# 3_DEBUG_SD__RTC.net
KiCad netlist of a schematic drawn in Altium Designer
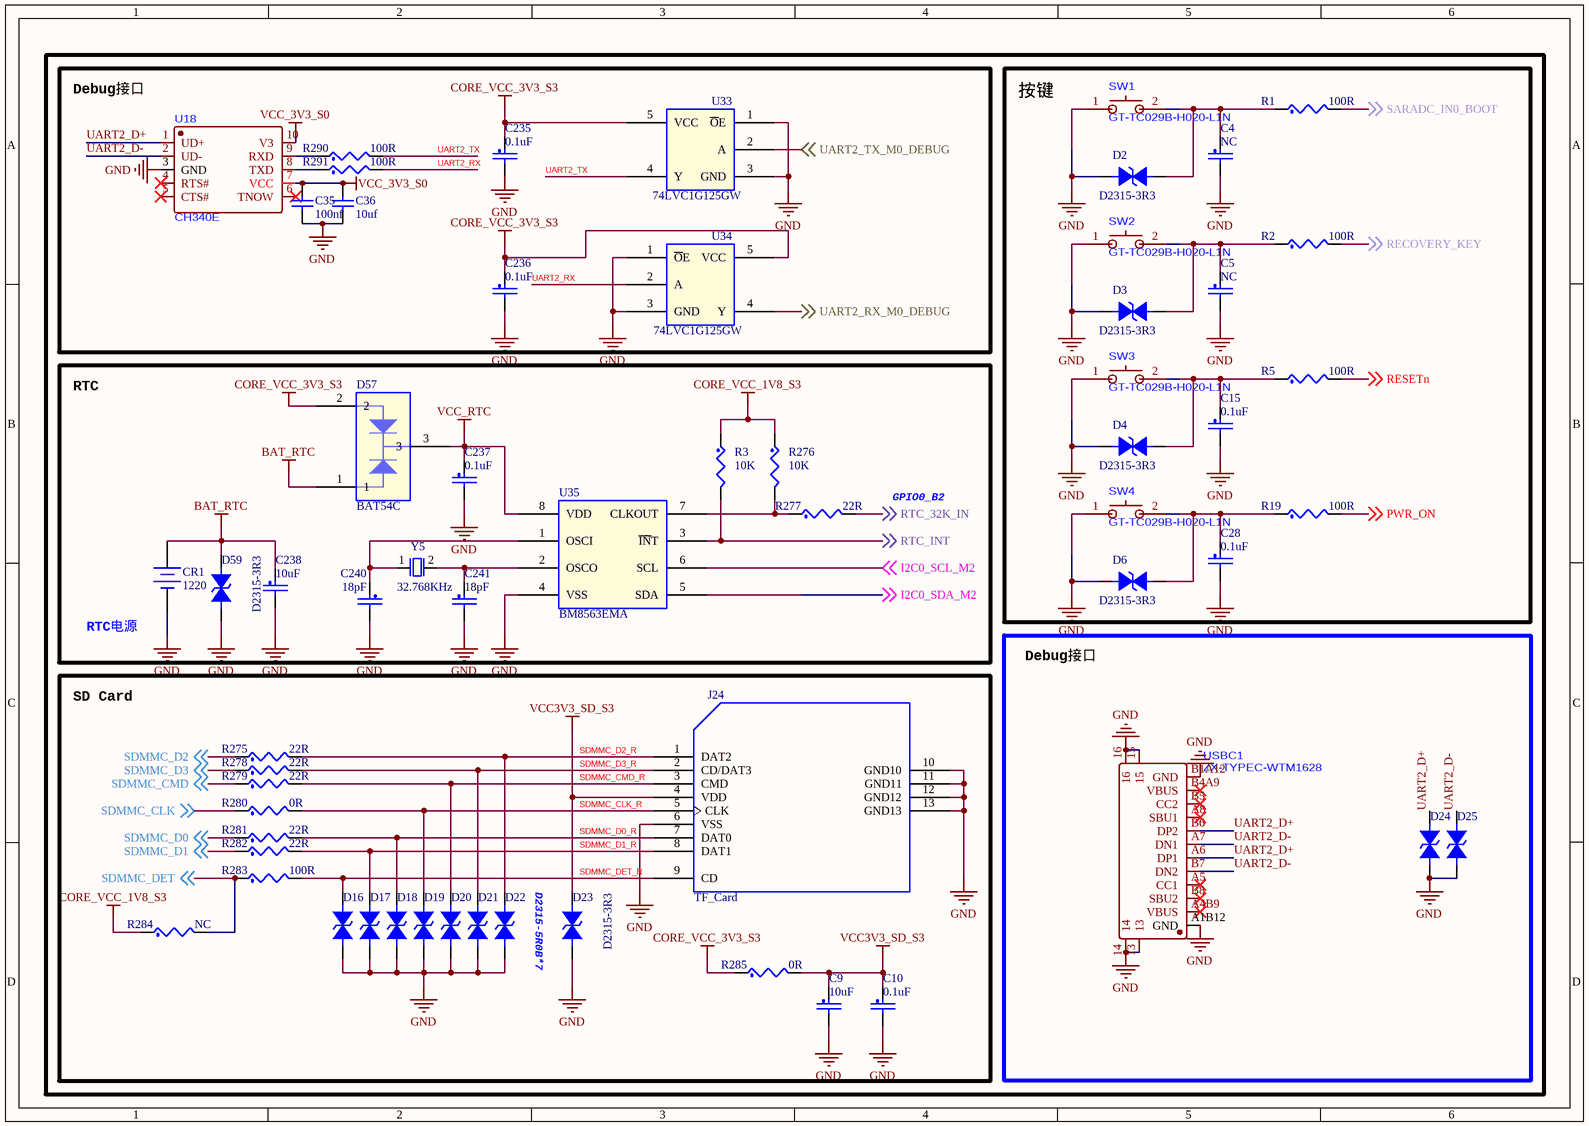
[diagram p0: 3.DEBUG_SD卡_RTC_按键.SchDoc]

(export (version "E")
  (design (tool "Eeschema 10.0.6"))
  (components
    (comp (ref "C4") (value "NC") (footprint "0.PCB1:C0402") (libsource (lib "RK3588底板") (part "CAP_NP")))
    (comp (ref "C5") (value "NC") (footprint "0.PCB1:C0402") (libsource (lib "RK3588底板") (part "CAP_NP")))
    (comp (ref "C9") (value "10uF") (footprint "0.PCB1:C0402") (libsource (lib "RK3588底板") (part "CAP_NP")))
    (comp (ref "C10") (value "0.1uF") (footprint "0.PCB1:C0402") (libsource (lib "RK3588底板") (part "CAP_NP")))
    (comp (ref "C15") (value "0.1uF") (footprint "0.PCB1:C0402") (libsource (lib "RK3588底板") (part "CAP_NP")))
    (comp (ref "C28") (value "0.1uF") (footprint "0.PCB1:C0402") (libsource (lib "RK3588底板") (part "CAP_NP")))
    (comp (ref "C35")
      (value "100nf")
      (footprint "0.PCB1:C0603_L")
      (description "贴片电容/MLCC电容")
      (libsource (lib "RK3588底板") (part "C"))
    )
    (comp (ref "C36")
      (value "10uf")
      (footprint "0.PCB1:C0603_L")
      (description "贴片电容/MLCC电容")
      (libsource (lib "RK3588底板") (part "C"))
    )
    (comp (ref "C235")
      (value "0.1uF")
      (footprint "0.PCB1:C0402")
      (libsource (lib "RK3588底板") (part "CAP_NP"))
    )
    (comp (ref "C236")
      (value "0.1uF")
      (footprint "0.PCB1:C0402")
      (libsource (lib "RK3588底板") (part "CAP_NP"))
    )
    (comp (ref "C237")
      (value "0.1uF")
      (footprint "0.PCB1:C0402")
      (libsource (lib "RK3588底板") (part "CAP_NP"))
    )
    (comp (ref "C238") (value "10uF") (footprint "0.PCB1:C0402") (libsource (lib "RK3588底板") (part "CAP_NP")))
    (comp (ref "C240") (value "18pF") (footprint "0.PCB1:C0402") (libsource (lib "RK3588底板") (part "CAP_NP")))
    (comp (ref "C241") (value "18pF") (footprint "0.PCB1:C0402") (libsource (lib "RK3588底板") (part "CAP_NP")))
    (comp (ref "CR1")
      (value "1220")
      (footprint "0.PCB1:CR1220_A")
      (description "微型电池")
      (libsource (lib "RK3588底板") (part "BAT_CR1220_CR2032"))
    )
    (comp (ref "D2")
      (value "D2315-3R3")
      (footprint "0.PCB1:esd0402")
      (libsource (lib "RK3588底板") (part "DIODE BI-DIR TRIG"))
    )
    (comp (ref "D3")
      (value "D2315-3R3")
      (footprint "0.PCB1:esd0402")
      (libsource (lib "RK3588底板") (part "DIODE BI-DIR TRIG"))
    )
    (comp (ref "D4")
      (value "D2315-3R3")
      (footprint "0.PCB1:esd0402")
      (libsource (lib "RK3588底板") (part "DIODE BI-DIR TRIG"))
    )
    (comp (ref "D6")
      (value "D2315-3R3")
      (footprint "0.PCB1:esd0402")
      (libsource (lib "RK3588底板") (part "DIODE BI-DIR TRIG"))
    )
    (comp (ref "D16")
      (value "D2315-5R0B")
      (footprint "0.PCB1:esd0402")
      (libsource (lib "RK3588底板") (part "DIODE BI-DIR TRIG"))
    )
    (comp (ref "D17")
      (value "D2315-5R0B")
      (footprint "0.PCB1:esd0402")
      (libsource (lib "RK3588底板") (part "DIODE BI-DIR TRIG"))
    )
    (comp (ref "D18")
      (value "D2315-5R0B")
      (footprint "0.PCB1:esd0402")
      (libsource (lib "RK3588底板") (part "DIODE BI-DIR TRIG"))
    )
    (comp (ref "D19")
      (value "D2315-5R0B")
      (footprint "0.PCB1:esd0402")
      (libsource (lib "RK3588底板") (part "DIODE BI-DIR TRIG"))
    )
    (comp (ref "D20")
      (value "D2315-5R0B")
      (footprint "0.PCB1:esd0402")
      (libsource (lib "RK3588底板") (part "DIODE BI-DIR TRIG"))
    )
    (comp (ref "D21")
      (value "D2315-5R0B")
      (footprint "0.PCB1:esd0402")
      (libsource (lib "RK3588底板") (part "DIODE BI-DIR TRIG"))
    )
    (comp (ref "D22")
      (value "D2315-5R0B")
      (footprint "0.PCB1:esd0402")
      (libsource (lib "RK3588底板") (part "DIODE BI-DIR TRIG"))
    )
    (comp (ref "D23")
      (value "D2315-3R3")
      (footprint "0.PCB1:esd0402")
      (libsource (lib "RK3588底板") (part "DIODE BI-DIR TRIG"))
    )
    (comp (ref "D24")
      (value "D2315-5R0B")
      (footprint "0.PCB1:esd0402")
      (libsource (lib "RK3588底板") (part "DIODE BI-DIR TRIG"))
    )
    (comp (ref "D25")
      (value "D2315-5R0B")
      (footprint "0.PCB1:esd0402")
      (libsource (lib "RK3588底板") (part "DIODE BI-DIR TRIG"))
    )
    (comp (ref "D57")
      (value "BAT54C")
      (footprint "0.PCB1:SOT23")
      (libsource (lib "RK3588底板") (part "BAT54C"))
    )
    (comp (ref "D59")
      (value "D2315-3R3")
      (footprint "0.PCB1:esd0402")
      (libsource (lib "RK3588底板") (part "DIODE BI-DIR TRIG"))
    )
    (comp (ref "J24")
      (value "TF_Card")
      (footprint "0.PCB1:TFCARD")
      (libsource (lib "RK3588底板") (part "TF_Card"))
    )
    (comp (ref "R1") (value "100R") (footprint "0.PCB1:R0402") (libsource (lib "RK3588底板") (part "RES")))
    (comp (ref "R2") (value "100R") (footprint "0.PCB1:R0402") (libsource (lib "RK3588底板") (part "RES")))
    (comp (ref "R3") (value "10K") (footprint "0.PCB1:R0402") (libsource (lib "RK3588底板") (part "RES")))
    (comp (ref "R5") (value "100R") (footprint "0.PCB1:R0402") (libsource (lib "RK3588底板") (part "RES")))
    (comp (ref "R19") (value "100R") (footprint "0.PCB1:R0402") (libsource (lib "RK3588底板") (part "RES")))
    (comp (ref "R275") (value "22R") (footprint "0.PCB1:R0402") (libsource (lib "RK3588底板") (part "RES")))
    (comp (ref "R276") (value "10K") (footprint "0.PCB1:R0402") (libsource (lib "RK3588底板") (part "RES")))
    (comp (ref "R277") (value "22R") (footprint "0.PCB1:R0402") (libsource (lib "RK3588底板") (part "RES")))
    (comp (ref "R278") (value "22R") (footprint "0.PCB1:R0402") (libsource (lib "RK3588底板") (part "RES")))
    (comp (ref "R279") (value "22R") (footprint "0.PCB1:R0402") (libsource (lib "RK3588底板") (part "RES")))
    (comp (ref "R280") (value "0R") (footprint "0.PCB1:R0402") (libsource (lib "RK3588底板") (part "RES")))
    (comp (ref "R281") (value "22R") (footprint "0.PCB1:R0402") (libsource (lib "RK3588底板") (part "RES")))
    (comp (ref "R282") (value "22R") (footprint "0.PCB1:R0402") (libsource (lib "RK3588底板") (part "RES")))
    (comp (ref "R283") (value "100R") (footprint "0.PCB1:R0402") (libsource (lib "RK3588底板") (part "RES")))
    (comp (ref "R284") (value "NC") (footprint "0.PCB1:R0402") (libsource (lib "RK3588底板") (part "RES")))
    (comp (ref "R285") (value "0R") (footprint "0.PCB1:R0402") (libsource (lib "RK3588底板") (part "RES")))
    (comp (ref "R290") (value "100R") (footprint "0.PCB1:R0402") (libsource (lib "RK3588底板") (part "RES")))
    (comp (ref "R291") (value "100R") (footprint "0.PCB1:R0402") (libsource (lib "RK3588底板") (part "RES")))
    (comp (ref "SW1")
      (value "GT-TC029B-H020-L1N")
      (footprint "0.PCB1:SW-SMD_L3.9-W2.9-P4.15-LS5.0")
      (libsource (lib "RK3588底板") (part "GT-TC029B-H020-L1N"))
    )
    (comp (ref "SW2")
      (value "GT-TC029B-H020-L1N")
      (footprint "0.PCB1:SW-SMD_L3.9-W2.9-P4.15-LS5.0")
      (libsource (lib "RK3588底板") (part "GT-TC029B-H020-L1N"))
    )
    (comp (ref "SW3")
      (value "GT-TC029B-H020-L1N")
      (footprint "0.PCB1:SW-SMD_L3.9-W2.9-P4.15-LS5.0")
      (libsource (lib "RK3588底板") (part "GT-TC029B-H020-L1N"))
    )
    (comp (ref "SW4")
      (value "GT-TC029B-H020-L1N")
      (footprint "0.PCB1:SW-SMD_L3.9-W2.9-P4.15-LS5.0")
      (libsource (lib "RK3588底板") (part "GT-TC029B-H020-L1N"))
    )
    (comp (ref "U18")
      (value "CH340E")
      (footprint "0.PCB1:MSOP-10_L3.0-W3.0-P0.50-LS5.0-BL")
      (libsource (lib "RK3588底板") (part "CH340E"))
    )
    (comp (ref "U33")
      (value "74LVC1G125GW")
      (footprint "0.PCB1:SOT-353")
      (libsource (lib "") (part "74LVC1G125_1"))
    )
    (comp (ref "U34")
      (value "74LVC1G125GW")
      (footprint "0.PCB1:SOT-353")
      (libsource (lib "RK3588底板") (part "74LVC1G125"))
    )
    (comp (ref "U35")
      (value "BM8563EMA")
      (footprint "0.PCB1:msop-8")
      (libsource (lib "RK3588底板") (part "HYM8563S"))
    )
    (comp (ref "USBC1")
      (value "ZX-TYPEC-WTM1628")
      (footprint "0.PCB1:USB-C-SMD_ZX-TYPEC-WTM1628")
      (libsource (lib "RK3588底板") (part "ZX-TYPEC-WTM1628"))
    )
    (comp (ref "Y5")
      (value "32.768KHz")
      (footprint "0.PCB1:3215")
      (libsource (lib "RK3588底板") (part "CRYSTAL_2P"))
    )
  )
  (nets
    (net (code "1") (name "/SDMMC_CLK_R") (class "Default")
      (node (ref "D19") (pin "2") (pinfunction "2_2") (pintype "passive"))
      (node (ref "J24") (pin "5") (pinfunction "CLK_5") (pintype "passive"))
      (node (ref "R280") (pin "2") (pinfunction "2_2") (pintype "passive"))
    )
    (net (code "2") (name "/SDMMC_CMD_R") (class "Default")
      (node (ref "D20") (pin "2") (pinfunction "2_2") (pintype "passive"))
      (node (ref "J24") (pin "3") (pinfunction "CMD_3") (pintype "passive"))
      (node (ref "R279") (pin "2") (pinfunction "2_2") (pintype "passive"))
    )
    (net (code "3") (name "/SDMMC_D0_R") (class "Default")
      (node (ref "D18") (pin "2") (pinfunction "2_2") (pintype "passive"))
      (node (ref "J24") (pin "7") (pinfunction "DAT0_7") (pintype "passive"))
      (node (ref "R281") (pin "2") (pinfunction "2_2") (pintype "passive"))
    )
    (net (code "4") (name "/SDMMC_D1_R") (class "Default")
      (node (ref "D17") (pin "2") (pinfunction "2_2") (pintype "passive"))
      (node (ref "J24") (pin "8") (pinfunction "DAT1_8") (pintype "passive"))
      (node (ref "R282") (pin "2") (pinfunction "2_2") (pintype "passive"))
    )
    (net (code "5") (name "/SDMMC_D2_R") (class "Default")
      (node (ref "D22") (pin "2") (pinfunction "2_2") (pintype "passive"))
      (node (ref "J24") (pin "1") (pinfunction "DAT2_1") (pintype "passive"))
      (node (ref "R275") (pin "2") (pinfunction "2_2") (pintype "passive"))
    )
    (net (code "6") (name "/SDMMC_D3_R") (class "Default")
      (node (ref "D21") (pin "2") (pinfunction "2_2") (pintype "passive"))
      (node (ref "J24") (pin "2") (pinfunction "CD/DAT3_2") (pintype "passive"))
      (node (ref "R278") (pin "2") (pinfunction "2_2") (pintype "passive"))
    )
    (net (code "7") (name "/SDMMC_DET_R") (class "Default")
      (node (ref "D16") (pin "2") (pinfunction "2_2") (pintype "passive"))
      (node (ref "J24") (pin "9") (pinfunction "CD_9") (pintype "passive"))
      (node (ref "R283") (pin "2") (pinfunction "2_2") (pintype "passive"))
    )
    (net (code "8") (name "/UART2_D+") (class "Default")
      (node (ref "D24") (pin "2") (pinfunction "2_2") (pintype "passive"))
      (node (ref "U18") (pin "1") (pinfunction "UD+_1") (pintype "passive"))
      (node (ref "USBC1") (pin "A6") (pinfunction "DP1_A6") (pintype "passive"))
      (node (ref "USBC1") (pin "B6") (pinfunction "DP2_B6") (pintype "passive"))
    )
    (net (code "9") (name "/UART2_D-") (class "Default")
      (node (ref "D25") (pin "2") (pinfunction "2_2") (pintype "passive"))
      (node (ref "U18") (pin "2") (pinfunction "UD-_2") (pintype "passive"))
      (node (ref "USBC1") (pin "A7") (pinfunction "DN1_A7") (pintype "passive"))
      (node (ref "USBC1") (pin "B7") (pinfunction "DN2_B7") (pintype "passive"))
    )
    (net (code "10") (name "/UART2_RX") (class "Default")
      (node (ref "R291") (pin "2") (pinfunction "2_2") (pintype "passive"))
      (node (ref "U34") (pin "2") (pinfunction "A_2") (pintype "passive"))
    )
    (net (code "11") (name "/UART2_TX") (class "Default")
      (node (ref "R290") (pin "2") (pinfunction "2_2") (pintype "passive"))
      (node (ref "U33") (pin "4") (pinfunction "Y_4") (pintype "passive"))
    )
    (net (code "12") (name "BAT_RTC") (class "Default")
      (node (ref "C238") (pin "1") (pinfunction "1_1") (pintype "passive"))
      (node (ref "CR1") (pin "1") (pinfunction "DC+_1") (pintype "passive"))
      (node (ref "D57") (pin "1") (pinfunction "1_1") (pintype "passive"))
      (node (ref "D59") (pin "1") (pinfunction "1_1") (pintype "passive"))
    )
    (net (code "13") (name "CORE_VCC_1V8_S3") (class "Default")
      (node (ref "R276") (pin "1") (pinfunction "1_1") (pintype "passive"))
      (node (ref "R284") (pin "1") (pinfunction "1_1") (pintype "passive"))
      (node (ref "R3") (pin "1") (pinfunction "1_1") (pintype "passive"))
    )
    (net (code "14") (name "CORE_VCC_3V3_S3") (class "Default")
      (node (ref "C235") (pin "1") (pinfunction "1_1") (pintype "passive"))
      (node (ref "C236") (pin "1") (pinfunction "1_1") (pintype "passive"))
      (node (ref "D57") (pin "2") (pinfunction "2_2") (pintype "passive"))
      (node (ref "R285") (pin "1") (pinfunction "1_1") (pintype "passive"))
      (node (ref "U33") (pin "5") (pinfunction "VCC_5") (pintype "passive"))
      (node (ref "U34") (pin "5") (pinfunction "VCC_5") (pintype "passive"))
    )
    (net (code "15") (name "GND") (class "Default")
      (node (ref "C10") (pin "2") (pinfunction "2_2") (pintype "passive"))
      (node (ref "C15") (pin "2") (pinfunction "2_2") (pintype "passive"))
      (node (ref "C235") (pin "2") (pinfunction "2_2") (pintype "passive"))
      (node (ref "C236") (pin "2") (pinfunction "2_2") (pintype "passive"))
      (node (ref "C237") (pin "2") (pinfunction "2_2") (pintype "passive"))
      (node (ref "C238") (pin "2") (pinfunction "2_2") (pintype "passive"))
      (node (ref "C240") (pin "2") (pinfunction "2_2") (pintype "passive"))
      (node (ref "C241") (pin "2") (pinfunction "2_2") (pintype "passive"))
      (node (ref "C28") (pin "2") (pinfunction "2_2") (pintype "passive"))
      (node (ref "C35") (pin "1") (pinfunction "1_1") (pintype "passive"))
      (node (ref "C36") (pin "1") (pinfunction "1_1") (pintype "passive"))
      (node (ref "C4") (pin "2") (pinfunction "2_2") (pintype "passive"))
      (node (ref "C5") (pin "2") (pinfunction "2_2") (pintype "passive"))
      (node (ref "C9") (pin "2") (pinfunction "2_2") (pintype "passive"))
      (node (ref "CR1") (pin "2") (pinfunction "DC-_2") (pintype "passive"))
      (node (ref "D16") (pin "1") (pinfunction "1_1") (pintype "passive"))
      (node (ref "D17") (pin "1") (pinfunction "1_1") (pintype "passive"))
      (node (ref "D18") (pin "1") (pinfunction "1_1") (pintype "passive"))
      (node (ref "D19") (pin "1") (pinfunction "1_1") (pintype "passive"))
      (node (ref "D2") (pin "1") (pinfunction "1_1") (pintype "passive"))
      (node (ref "D20") (pin "1") (pinfunction "1_1") (pintype "passive"))
      (node (ref "D21") (pin "1") (pinfunction "1_1") (pintype "passive"))
      (node (ref "D22") (pin "1") (pinfunction "1_1") (pintype "passive"))
      (node (ref "D23") (pin "2") (pinfunction "2_2") (pintype "passive"))
      (node (ref "D24") (pin "1") (pinfunction "1_1") (pintype "passive"))
      (node (ref "D25") (pin "1") (pinfunction "1_1") (pintype "passive"))
      (node (ref "D3") (pin "1") (pinfunction "1_1") (pintype "passive"))
      (node (ref "D4") (pin "1") (pinfunction "1_1") (pintype "passive"))
      (node (ref "D59") (pin "2") (pinfunction "2_2") (pintype "passive"))
      (node (ref "D6") (pin "1") (pinfunction "1_1") (pintype "passive"))
      (node (ref "J24") (pin "10") (pinfunction "GND10_10") (pintype "passive"))
      (node (ref "J24") (pin "11") (pinfunction "GND11_11") (pintype "passive"))
      (node (ref "J24") (pin "12") (pinfunction "GND12_12") (pintype "passive"))
      (node (ref "J24") (pin "13") (pinfunction "GND13_13") (pintype "passive"))
      (node (ref "J24") (pin "6") (pinfunction "VSS_6") (pintype "power_in"))
      (node (ref "SW1") (pin "1") (pinfunction "1_1") (pintype "passive"))
      (node (ref "SW2") (pin "1") (pinfunction "1_1") (pintype "passive"))
      (node (ref "SW3") (pin "1") (pinfunction "1_1") (pintype "passive"))
      (node (ref "SW4") (pin "1") (pinfunction "1_1") (pintype "passive"))
      (node (ref "U18") (pin "3") (pinfunction "GND_3") (pintype "passive"))
      (node (ref "U33") (pin "1") (pinfunction "~{O}E_1") (pintype "passive"))
      (node (ref "U33") (pin "3") (pinfunction "GND_3") (pintype "passive"))
      (node (ref "U34") (pin "1") (pinfunction "~{O}E_1") (pintype "passive"))
      (node (ref "U34") (pin "3") (pinfunction "GND_3") (pintype "passive"))
      (node (ref "U35") (pin "4") (pinfunction "VSS_4") (pintype "passive"))
      (node (ref "USBC1") (pin "13") (pinfunction "13_13") (pintype "passive"))
      (node (ref "USBC1") (pin "14") (pinfunction "14_14") (pintype "passive"))
      (node (ref "USBC1") (pin "15") (pinfunction "15_15") (pintype "passive"))
      (node (ref "USBC1") (pin "16") (pinfunction "16_16") (pintype "passive"))
      (node (ref "USBC1") (pin "A1B12") (pinfunction "GND_A1B12") (pintype "passive"))
      (node (ref "USBC1") (pin "B1A12") (pinfunction "GND_B1A12") (pintype "passive"))
    )
    (net (code "16") (name "I2C0_SCL_M2") (class "Default")
      (node (ref "U35") (pin "6") (pinfunction "SCL_6") (pintype "passive"))
    )
    (net (code "17") (name "I2C0_SDA_M2") (class "Default")
      (node (ref "U35") (pin "5") (pinfunction "SDA_5") (pintype "passive"))
    )
    (net (code "18") (name "Net-(C4-Pad1)") (class "Default")
      (node (ref "C4") (pin "1") (pinfunction "1_1") (pintype "passive"))
      (node (ref "D2") (pin "2") (pinfunction "2_2") (pintype "passive"))
      (node (ref "R1") (pin "1") (pinfunction "1_1") (pintype "passive"))
      (node (ref "SW1") (pin "2") (pinfunction "2_2") (pintype "passive"))
    )
    (net (code "19") (name "Net-(C5-Pad1)") (class "Default")
      (node (ref "C5") (pin "1") (pinfunction "1_1") (pintype "passive"))
      (node (ref "D3") (pin "2") (pinfunction "2_2") (pintype "passive"))
      (node (ref "R2") (pin "1") (pinfunction "1_1") (pintype "passive"))
      (node (ref "SW2") (pin "2") (pinfunction "2_2") (pintype "passive"))
    )
    (net (code "20") (name "Net-(C15-Pad1)") (class "Default")
      (node (ref "C15") (pin "1") (pinfunction "1_1") (pintype "passive"))
      (node (ref "D4") (pin "2") (pinfunction "2_2") (pintype "passive"))
      (node (ref "R5") (pin "1") (pinfunction "1_1") (pintype "passive"))
      (node (ref "SW3") (pin "2") (pinfunction "2_2") (pintype "passive"))
    )
    (net (code "21") (name "Net-(C28-Pad1)") (class "Default")
      (node (ref "C28") (pin "1") (pinfunction "1_1") (pintype "passive"))
      (node (ref "D6") (pin "2") (pinfunction "2_2") (pintype "passive"))
      (node (ref "R19") (pin "1") (pinfunction "1_1") (pintype "passive"))
      (node (ref "SW4") (pin "2") (pinfunction "2_2") (pintype "passive"))
    )
    (net (code "22") (name "Net-(U18-RXD)") (class "Default")
      (node (ref "R290") (pin "1") (pinfunction "1_1") (pintype "passive"))
      (node (ref "U18") (pin "9") (pinfunction "RXD_9") (pintype "passive"))
    )
    (net (code "23") (name "Net-(U18-TXD)") (class "Default")
      (node (ref "R291") (pin "1") (pinfunction "1_1") (pintype "passive"))
      (node (ref "U18") (pin "8") (pinfunction "TXD_8") (pintype "passive"))
    )
    (net (code "24") (name "Net-(U35-CLKOUT)") (class "Default")
      (node (ref "R276") (pin "2") (pinfunction "2_2") (pintype "passive"))
      (node (ref "R277") (pin "1") (pinfunction "1_1") (pintype "passive"))
      (node (ref "U35") (pin "7") (pinfunction "CLKOUT_7") (pintype "passive"))
    )
    (net (code "25") (name "Net-(U35-OSCI)") (class "Default")
      (node (ref "C240") (pin "1") (pinfunction "1_1") (pintype "passive"))
      (node (ref "U35") (pin "1") (pinfunction "OSCI_1") (pintype "passive"))
      (node (ref "Y5") (pin "1") (pinfunction "1_1") (pintype "passive"))
    )
    (net (code "26") (name "Net-(U35-OSCO)") (class "Default")
      (node (ref "C241") (pin "1") (pinfunction "1_1") (pintype "passive"))
      (node (ref "U35") (pin "2") (pinfunction "OSCO_2") (pintype "passive"))
      (node (ref "Y5") (pin "2") (pinfunction "2_2") (pintype "passive"))
    )
    (net (code "27") (name "PWR_ON") (class "Default")
      (node (ref "R19") (pin "2") (pinfunction "2_2") (pintype "passive"))
    )
    (net (code "28") (name "RECOVERY_KEY") (class "Default")
      (node (ref "R2") (pin "2") (pinfunction "2_2") (pintype "passive"))
    )
    (net (code "29") (name "RESETn") (class "Default")
      (node (ref "R5") (pin "2") (pinfunction "2_2") (pintype "passive"))
    )
    (net (code "30") (name "RTC_32K_IN") (class "Default")
      (node (ref "R277") (pin "2") (pinfunction "2_2") (pintype "passive"))
    )
    (net (code "31") (name "RTC_INT") (class "Default")
      (node (ref "R3") (pin "2") (pinfunction "2_2") (pintype "passive"))
      (node (ref "U35") (pin "3") (pinfunction "~{IN}T_3") (pintype "passive"))
    )
    (net (code "32") (name "SARADC_IN0_BOOT") (class "Default")
      (node (ref "R1") (pin "2") (pinfunction "2_2") (pintype "passive"))
    )
    (net (code "33") (name "SDMMC_CLK") (class "Default")
      (node (ref "R280") (pin "1") (pinfunction "1_1") (pintype "passive"))
    )
    (net (code "34") (name "SDMMC_CMD") (class "Default")
      (node (ref "R279") (pin "1") (pinfunction "1_1") (pintype "passive"))
    )
    (net (code "35") (name "SDMMC_D0") (class "Default")
      (node (ref "R281") (pin "1") (pinfunction "1_1") (pintype "passive"))
    )
    (net (code "36") (name "SDMMC_D1") (class "Default")
      (node (ref "R282") (pin "1") (pinfunction "1_1") (pintype "passive"))
    )
    (net (code "37") (name "SDMMC_D2") (class "Default")
      (node (ref "R275") (pin "1") (pinfunction "1_1") (pintype "passive"))
    )
    (net (code "38") (name "SDMMC_D3") (class "Default")
      (node (ref "R278") (pin "1") (pinfunction "1_1") (pintype "passive"))
    )
    (net (code "39") (name "SDMMC_DET") (class "Default")
      (node (ref "R283") (pin "1") (pinfunction "1_1") (pintype "passive"))
      (node (ref "R284") (pin "2") (pinfunction "2_2") (pintype "passive"))
    )
    (net (code "40") (name "UART2_RX_M0_DEBUG") (class "Default")
      (node (ref "U34") (pin "4") (pinfunction "Y_4") (pintype "passive"))
    )
    (net (code "41") (name "UART2_TX_M0_DEBUG") (class "Default")
      (node (ref "U33") (pin "2") (pinfunction "A_2") (pintype "passive"))
    )
    (net (code "42") (name "VCC3V3_SD_S3") (class "Default")
      (node (ref "C10") (pin "1") (pinfunction "1_1") (pintype "passive"))
      (node (ref "C9") (pin "1") (pinfunction "1_1") (pintype "passive"))
      (node (ref "D23") (pin "1") (pinfunction "1_1") (pintype "passive"))
      (node (ref "J24") (pin "4") (pinfunction "VDD_4") (pintype "power_in"))
      (node (ref "R285") (pin "2") (pinfunction "2_2") (pintype "passive"))
    )
    (net (code "43") (name "VCC_3V3_S0") (class "Default")
      (node (ref "C35") (pin "2") (pinfunction "2_2") (pintype "passive"))
      (node (ref "C36") (pin "2") (pinfunction "2_2") (pintype "passive"))
      (node (ref "U18") (pin "10") (pinfunction "V3_10") (pintype "passive"))
      (node (ref "U18") (pin "7") (pinfunction "VCC_7") (pintype "passive"))
    )
    (net (code "44") (name "VCC_RTC") (class "Default")
      (node (ref "C237") (pin "1") (pinfunction "1_1") (pintype "passive"))
      (node (ref "D57") (pin "3") (pinfunction "3_3") (pintype "passive"))
      (node (ref "U35") (pin "8") (pinfunction "VDD_8") (pintype "passive"))
    )
    (net (code "45") (name "unconnected-(U18-CTS#-Pad5)") (class "Default")
      (node (ref "U18") (pin "5") (pinfunction "CTS#_5") (pintype "passive+no_connect"))
    )
    (net (code "46") (name "unconnected-(U18-RTS#-Pad4)") (class "Default")
      (node (ref "U18") (pin "4") (pinfunction "RTS#_4") (pintype "passive+no_connect"))
    )
    (net (code "47") (name "unconnected-(U18-TNOW-Pad6)") (class "Default")
      (node (ref "U18") (pin "6") (pinfunction "TNOW_6") (pintype "passive+no_connect"))
    )
    (net (code "48") (name "unconnected-(USBC1-CC1-PadA5)") (class "Default")
      (node (ref "USBC1") (pin "A5") (pinfunction "CC1_A5") (pintype "passive+no_connect"))
    )
    (net (code "49") (name "unconnected-(USBC1-CC2-PadB5)") (class "Default")
      (node (ref "USBC1") (pin "B5") (pinfunction "CC2_B5") (pintype "passive+no_connect"))
    )
    (net (code "50") (name "unconnected-(USBC1-SBU1-PadA8)") (class "Default")
      (node (ref "USBC1") (pin "A8") (pinfunction "SBU1_A8") (pintype "passive+no_connect"))
    )
    (net (code "51") (name "unconnected-(USBC1-SBU2-PadB8)") (class "Default")
      (node (ref "USBC1") (pin "B8") (pinfunction "SBU2_B8") (pintype "passive+no_connect"))
    )
    (net (code "52") (name "unconnected-(USBC1-VBUS-PadA4B9)") (class "Default")
      (node (ref "USBC1") (pin "A4B9") (pinfunction "VBUS_A4B9") (pintype "passive+no_connect"))
    )
    (net (code "53") (name "unconnected-(USBC1-VBUS-PadB4A9)") (class "Default")
      (node (ref "USBC1") (pin "B4A9") (pinfunction "VBUS_B4A9") (pintype "passive+no_connect"))
    )
  )
)
